# L-Stick_sheet3_misc.net
KiCad netlist of a schematic drawn in Altium Designer
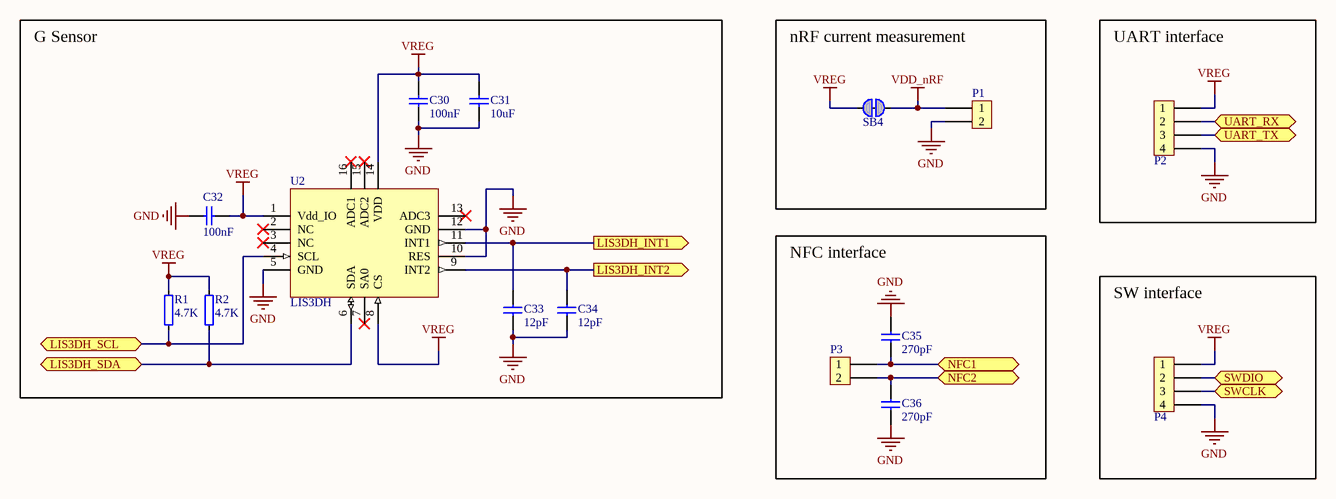
[diagram p0: L-Stick_sheet3_misc.SchDoc]

(export (version "E")
  (design (tool "Eeschema 10.0.6"))
  (components
    (comp (ref "C30")
      (value "100nF")
      (footprint "0402C")
      (description "Capacitor")
      (libsource (lib "L-Stick") (part "CAP_0402"))
    )
    (comp (ref "C31")
      (value "10uF")
      (footprint "0603C")
      (description "Capacitor")
      (libsource (lib "L-Stick") (part "CAP_0603"))
    )
    (comp (ref "C32")
      (value "100nF")
      (footprint "0402C")
      (description "Capacitor")
      (libsource (lib "L-Stick") (part "CAP_0402"))
    )
    (comp (ref "C33")
      (value "12pF")
      (footprint "0402C")
      (description "Capacitor")
      (libsource (lib "L-Stick") (part "CAP_0402"))
    )
    (comp (ref "C34")
      (value "12pF")
      (footprint "0402C")
      (description "Capacitor")
      (libsource (lib "L-Stick") (part "CAP_0402"))
    )
    (comp (ref "C35")
      (value "270pF")
      (footprint "0402C")
      (description "Capacitor")
      (libsource (lib "L-Stick") (part "CAP_0402"))
    )
    (comp (ref "C36")
      (value "270pF")
      (footprint "0402C")
      (description "Capacitor")
      (libsource (lib "L-Stick") (part "CAP_0402"))
    )
    (comp (ref "P1")
      (value "~")
      (footprint "LEG_2")
      (description "External Solder Pad")
      (libsource (lib "L-Stick") (part "LEG_2"))
    )
    (comp (ref "P2")
      (value "Header_4_2.54")
      (footprint "HEADER_4")
      (libsource (lib "L-Stick") (part "Header_4"))
    )
    (comp (ref "P3")
      (value "~")
      (footprint "TP_2x1mm_TH")
      (description "External Solder Pad")
      (libsource (lib "") (part "LEG_2_1"))
    )
    (comp (ref "P4")
      (value "Header_4_2.54")
      (footprint "HEADER_4")
      (libsource (lib "L-Stick") (part "Header_4"))
    )
    (comp (ref "R1")
      (value "4.7K")
      (footprint "0402R")
      (description "Resistor")
      (libsource (lib "L-Stick") (part "RES_0402"))
    )
    (comp (ref "R2")
      (value "4.7K")
      (footprint "0402R")
      (description "Resistor")
      (libsource (lib "L-Stick") (part "RES_0402"))
    )
    (comp (ref "SB4")
      (value "Solderbridge")
      (footprint "Solderbridge_Shorted")
      (description "Shorted Solderbridge")
      (libsource (lib "L-Stick") (part "SOLDERBRIDGE_SHORTED"))
    )
    (comp (ref "U2")
      (value "LIS3DH")
      (footprint "LGA-16")
      (description "Chip, LIS3DH, 3-axis - ±2g/±4g/±8g/±16g digital output femto accelerometer")
      (libsource (lib "L-Stick") (part "LIS3DH"))
    )
  )
  (nets
    (net (code "1") (name "/LIS3DH_INT1") (class "Default")
      (node (ref "C33") (pin "2") (pinfunction "2_2") (pintype "passive"))
      (node (ref "U2") (pin "11") (pinfunction "INT1_11") (pintype "output"))
    )
    (net (code "2") (name "/LIS3DH_INT2") (class "Default")
      (node (ref "C34") (pin "2") (pinfunction "2_2") (pintype "passive"))
      (node (ref "U2") (pin "9") (pinfunction "INT2_9") (pintype "output"))
    )
    (net (code "3") (name "/LIS3DH_SCL") (class "Default")
      (node (ref "R1") (pin "1") (pinfunction "1_1") (pintype "passive"))
      (node (ref "U2") (pin "4") (pinfunction "SCL_4") (pintype "input"))
    )
    (net (code "4") (name "/LIS3DH_SDA") (class "Default")
      (node (ref "R2") (pin "1") (pinfunction "1_1") (pintype "passive"))
      (node (ref "U2") (pin "6") (pinfunction "SDA_6") (pintype "bidirectional"))
    )
    (net (code "5") (name "/NFC1") (class "Default")
      (node (ref "C35") (pin "1") (pinfunction "1_1") (pintype "passive"))
      (node (ref "P3") (pin "1") (pinfunction "1_1") (pintype "passive"))
    )
    (net (code "6") (name "/NFC2") (class "Default")
      (node (ref "C36") (pin "2") (pinfunction "2_2") (pintype "passive"))
      (node (ref "P3") (pin "2") (pinfunction "2_2") (pintype "passive"))
    )
    (net (code "7") (name "/SWCLK") (class "Default")
      (node (ref "P4") (pin "3") (pinfunction "3_3") (pintype "passive"))
    )
    (net (code "8") (name "/SWDIO") (class "Default")
      (node (ref "P4") (pin "2") (pinfunction "2_2") (pintype "passive"))
    )
    (net (code "9") (name "/UART_RX") (class "Default")
      (node (ref "P2") (pin "2") (pinfunction "2_2") (pintype "passive"))
    )
    (net (code "10") (name "/UART_TX") (class "Default")
      (node (ref "P2") (pin "3") (pinfunction "3_3") (pintype "passive"))
    )
    (net (code "11") (name "GND") (class "Default")
      (node (ref "C30") (pin "1") (pinfunction "1_1") (pintype "passive"))
      (node (ref "C31") (pin "1") (pinfunction "1_1") (pintype "passive"))
      (node (ref "C32") (pin "1") (pinfunction "1_1") (pintype "passive"))
      (node (ref "C33") (pin "1") (pinfunction "1_1") (pintype "passive"))
      (node (ref "C34") (pin "1") (pinfunction "1_1") (pintype "passive"))
      (node (ref "C35") (pin "2") (pinfunction "2_2") (pintype "passive"))
      (node (ref "C36") (pin "1") (pinfunction "1_1") (pintype "passive"))
      (node (ref "P1") (pin "2") (pinfunction "2_2") (pintype "passive"))
      (node (ref "P2") (pin "4") (pinfunction "4_4") (pintype "passive"))
      (node (ref "P4") (pin "4") (pinfunction "4_4") (pintype "passive"))
      (node (ref "U2") (pin "10") (pinfunction "RES_10") (pintype "power_in"))
      (node (ref "U2") (pin "12") (pinfunction "GND_12") (pintype "passive"))
      (node (ref "U2") (pin "5") (pinfunction "GND_5") (pintype "power_in"))
    )
    (net (code "12") (name "VDD_nRF") (class "Default")
      (node (ref "P1") (pin "1") (pinfunction "1_1") (pintype "passive"))
      (node (ref "SB4") (pin "2") (pinfunction "2_2") (pintype "passive"))
    )
    (net (code "13") (name "VREG") (class "Default")
      (node (ref "C30") (pin "2") (pinfunction "2_2") (pintype "passive"))
      (node (ref "C31") (pin "2") (pinfunction "2_2") (pintype "passive"))
      (node (ref "C32") (pin "2") (pinfunction "2_2") (pintype "passive"))
      (node (ref "P2") (pin "1") (pinfunction "1_1") (pintype "passive"))
      (node (ref "P4") (pin "1") (pinfunction "1_1") (pintype "passive"))
      (node (ref "R1") (pin "2") (pinfunction "2_2") (pintype "passive"))
      (node (ref "R2") (pin "2") (pinfunction "2_2") (pintype "passive"))
      (node (ref "SB4") (pin "1") (pinfunction "1_1") (pintype "passive"))
      (node (ref "U2") (pin "1") (pinfunction "Vdd_IO_1") (pintype "power_in"))
      (node (ref "U2") (pin "14") (pinfunction "VDD_14") (pintype "power_in"))
      (node (ref "U2") (pin "8") (pinfunction "CS_8") (pintype "input"))
    )
    (net (code "14") (name "unconnected-(U2-ADC1-Pad16)") (class "Default")
      (node (ref "U2") (pin "16") (pinfunction "ADC1_16") (pintype "power_in+no_connect"))
    )
    (net (code "15") (name "unconnected-(U2-ADC2-Pad15)") (class "Default")
      (node (ref "U2") (pin "15") (pinfunction "ADC2_15") (pintype "power_in+no_connect"))
    )
    (net (code "16") (name "unconnected-(U2-ADC3-Pad13)") (class "Default")
      (node (ref "U2") (pin "13") (pinfunction "ADC3_13") (pintype "power_in+no_connect"))
    )
    (net (code "17") (name "unconnected-(U2-NC-Pad2)") (class "Default")
      (node (ref "U2") (pin "2") (pinfunction "NC_2") (pintype "power_in+no_connect"))
    )
    (net (code "18") (name "unconnected-(U2-NC-Pad3)") (class "Default")
      (node (ref "U2") (pin "3") (pinfunction "NC_3") (pintype "power_in+no_connect"))
    )
    (net (code "19") (name "unconnected-(U2-SA0-Pad7)") (class "Default")
      (node (ref "U2") (pin "7") (pinfunction "SA0_7") (pintype "power_in+no_connect"))
    )
  )
)
